# tailbrake.net
KiCad netlist of a schematic drawn in EAGLE
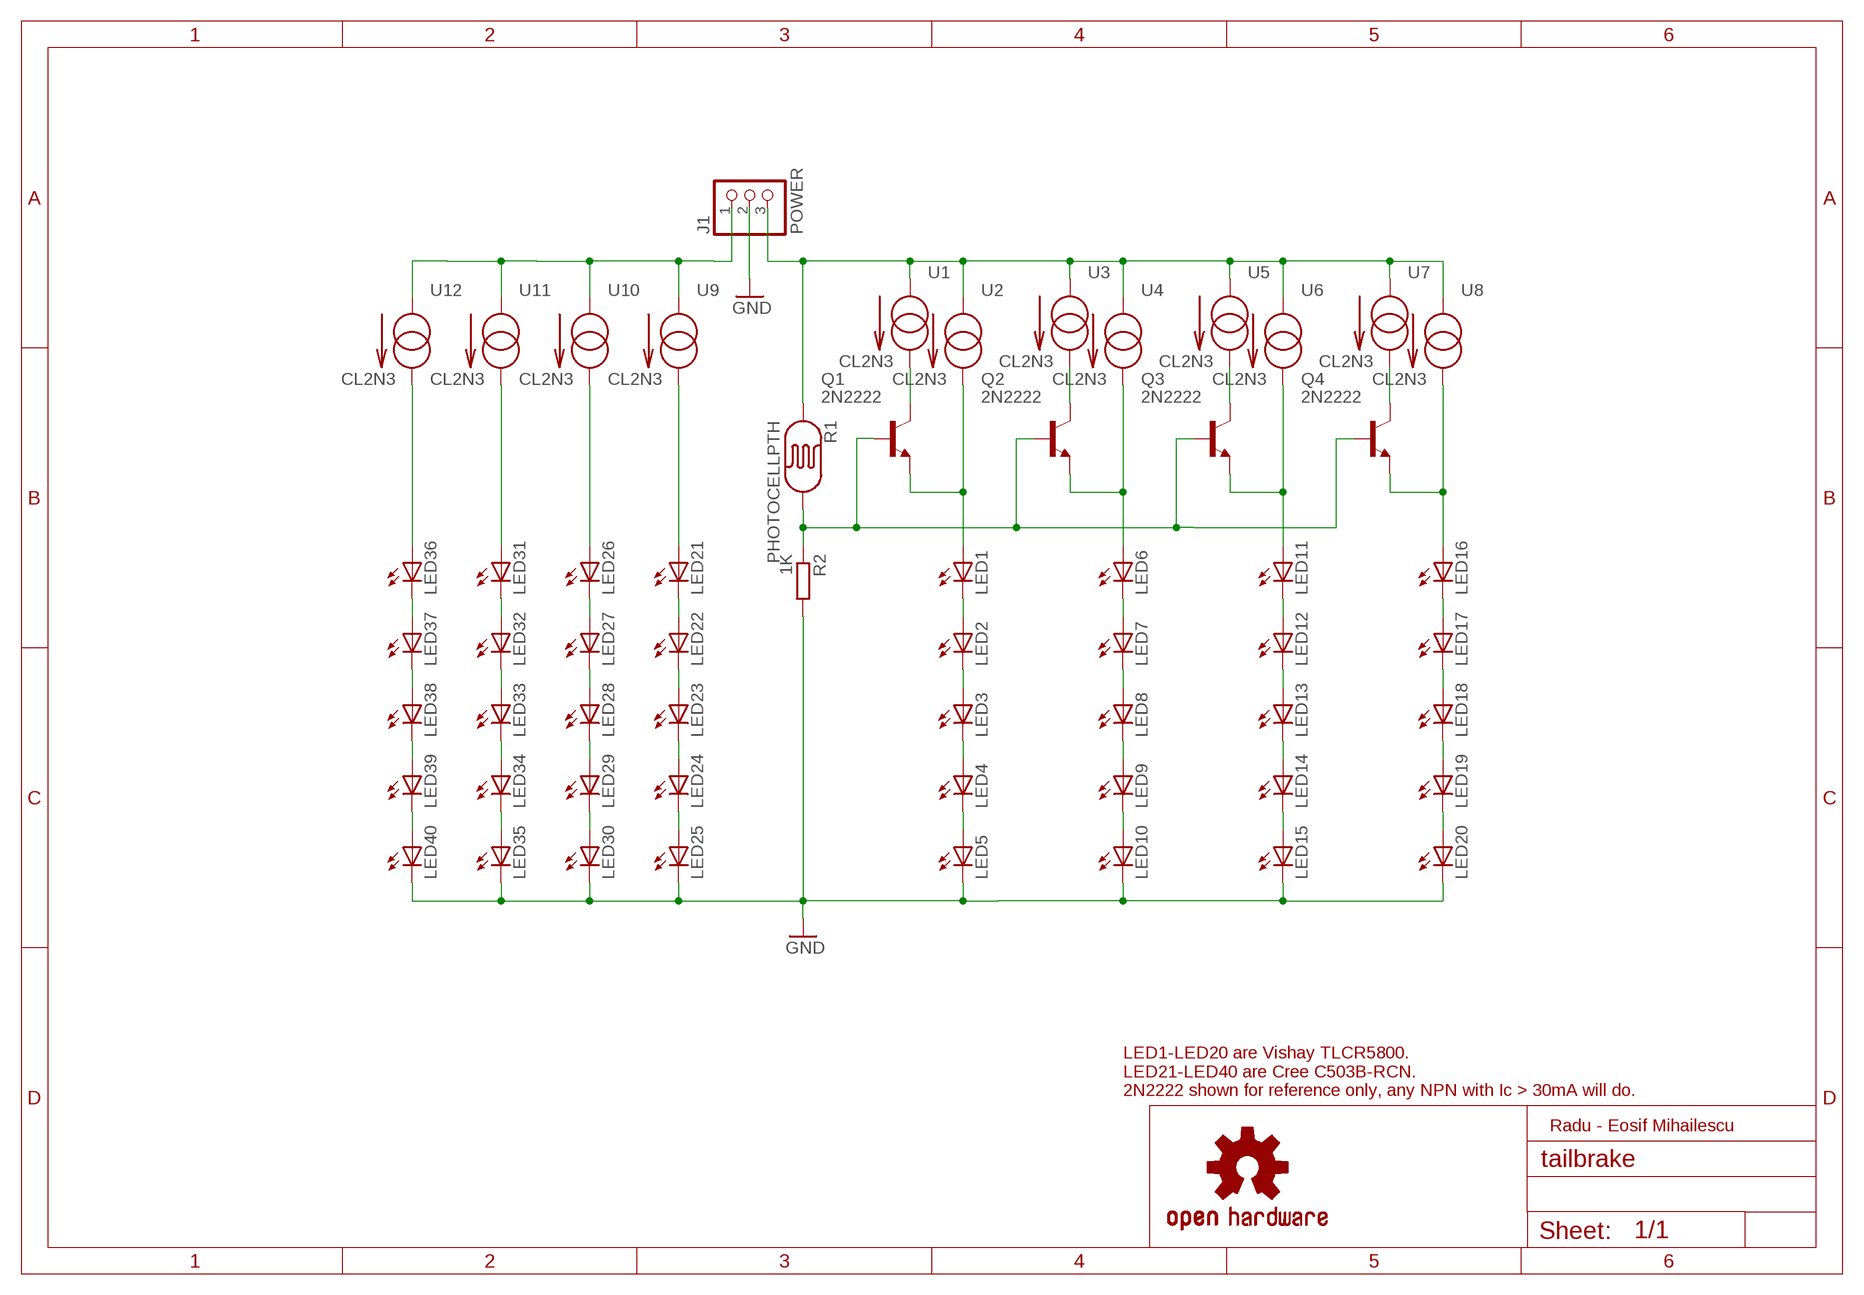
[diagram p0: schematic, sheet 1]

(export (version "E")
  (design (tool "Eeschema 10.0.6"))
  (components
    (comp (ref "J1")
      (value "POWER")
      (footprint "eagle-import:1X03_90")
      (libsource (lib "eagle-import") (part "PINHD-1X3/90"))
    )
    (comp (ref "LED1")
      (value "LED5MM")
      (footprint "eagle-import:LED5MM")
      (libsource (lib "eagle-import") (part "LED5MM"))
    )
    (comp (ref "LED2")
      (value "LED5MM")
      (footprint "eagle-import:LED5MM")
      (libsource (lib "eagle-import") (part "LED5MM"))
    )
    (comp (ref "LED3")
      (value "LED5MM")
      (footprint "eagle-import:LED5MM")
      (libsource (lib "eagle-import") (part "LED5MM"))
    )
    (comp (ref "LED4")
      (value "LED5MM")
      (footprint "eagle-import:LED5MM")
      (libsource (lib "eagle-import") (part "LED5MM"))
    )
    (comp (ref "LED5")
      (value "LED5MM")
      (footprint "eagle-import:LED5MM")
      (libsource (lib "eagle-import") (part "LED5MM"))
    )
    (comp (ref "LED6")
      (value "LED5MM")
      (footprint "eagle-import:LED5MM")
      (libsource (lib "eagle-import") (part "LED5MM"))
    )
    (comp (ref "LED7")
      (value "LED5MM")
      (footprint "eagle-import:LED5MM")
      (libsource (lib "eagle-import") (part "LED5MM"))
    )
    (comp (ref "LED8")
      (value "LED5MM")
      (footprint "eagle-import:LED5MM")
      (libsource (lib "eagle-import") (part "LED5MM"))
    )
    (comp (ref "LED9")
      (value "LED5MM")
      (footprint "eagle-import:LED5MM")
      (libsource (lib "eagle-import") (part "LED5MM"))
    )
    (comp (ref "LED10")
      (value "LED5MM")
      (footprint "eagle-import:LED5MM")
      (libsource (lib "eagle-import") (part "LED5MM"))
    )
    (comp (ref "LED11")
      (value "LED5MM")
      (footprint "eagle-import:LED5MM")
      (libsource (lib "eagle-import") (part "LED5MM"))
    )
    (comp (ref "LED12")
      (value "LED5MM")
      (footprint "eagle-import:LED5MM")
      (libsource (lib "eagle-import") (part "LED5MM"))
    )
    (comp (ref "LED13")
      (value "LED5MM")
      (footprint "eagle-import:LED5MM")
      (libsource (lib "eagle-import") (part "LED5MM"))
    )
    (comp (ref "LED14")
      (value "LED5MM")
      (footprint "eagle-import:LED5MM")
      (libsource (lib "eagle-import") (part "LED5MM"))
    )
    (comp (ref "LED15")
      (value "LED5MM")
      (footprint "eagle-import:LED5MM")
      (libsource (lib "eagle-import") (part "LED5MM"))
    )
    (comp (ref "LED16")
      (value "LED5MM")
      (footprint "eagle-import:LED5MM")
      (libsource (lib "eagle-import") (part "LED5MM"))
    )
    (comp (ref "LED17")
      (value "LED5MM")
      (footprint "eagle-import:LED5MM")
      (libsource (lib "eagle-import") (part "LED5MM"))
    )
    (comp (ref "LED18")
      (value "LED5MM")
      (footprint "eagle-import:LED5MM")
      (libsource (lib "eagle-import") (part "LED5MM"))
    )
    (comp (ref "LED19")
      (value "LED5MM")
      (footprint "eagle-import:LED5MM")
      (libsource (lib "eagle-import") (part "LED5MM"))
    )
    (comp (ref "LED20")
      (value "LED5MM")
      (footprint "eagle-import:LED5MM")
      (libsource (lib "eagle-import") (part "LED5MM"))
    )
    (comp (ref "LED21")
      (value "LED5MM")
      (footprint "eagle-import:LED5MM")
      (libsource (lib "eagle-import") (part "LED5MM"))
    )
    (comp (ref "LED22")
      (value "LED5MM")
      (footprint "eagle-import:LED5MM")
      (libsource (lib "eagle-import") (part "LED5MM"))
    )
    (comp (ref "LED23")
      (value "LED5MM")
      (footprint "eagle-import:LED5MM")
      (libsource (lib "eagle-import") (part "LED5MM"))
    )
    (comp (ref "LED24")
      (value "LED5MM")
      (footprint "eagle-import:LED5MM")
      (libsource (lib "eagle-import") (part "LED5MM"))
    )
    (comp (ref "LED25")
      (value "LED5MM")
      (footprint "eagle-import:LED5MM")
      (libsource (lib "eagle-import") (part "LED5MM"))
    )
    (comp (ref "LED26")
      (value "LED5MM")
      (footprint "eagle-import:LED5MM")
      (libsource (lib "eagle-import") (part "LED5MM"))
    )
    (comp (ref "LED27")
      (value "LED5MM")
      (footprint "eagle-import:LED5MM")
      (libsource (lib "eagle-import") (part "LED5MM"))
    )
    (comp (ref "LED28")
      (value "LED5MM")
      (footprint "eagle-import:LED5MM")
      (libsource (lib "eagle-import") (part "LED5MM"))
    )
    (comp (ref "LED29")
      (value "LED5MM")
      (footprint "eagle-import:LED5MM")
      (libsource (lib "eagle-import") (part "LED5MM"))
    )
    (comp (ref "LED30")
      (value "LED5MM")
      (footprint "eagle-import:LED5MM")
      (libsource (lib "eagle-import") (part "LED5MM"))
    )
    (comp (ref "LED31")
      (value "LED5MM")
      (footprint "eagle-import:LED5MM")
      (libsource (lib "eagle-import") (part "LED5MM"))
    )
    (comp (ref "LED32")
      (value "LED5MM")
      (footprint "eagle-import:LED5MM")
      (libsource (lib "eagle-import") (part "LED5MM"))
    )
    (comp (ref "LED33")
      (value "LED5MM")
      (footprint "eagle-import:LED5MM")
      (libsource (lib "eagle-import") (part "LED5MM"))
    )
    (comp (ref "LED34")
      (value "LED5MM")
      (footprint "eagle-import:LED5MM")
      (libsource (lib "eagle-import") (part "LED5MM"))
    )
    (comp (ref "LED35")
      (value "LED5MM")
      (footprint "eagle-import:LED5MM")
      (libsource (lib "eagle-import") (part "LED5MM"))
    )
    (comp (ref "LED36")
      (value "LED5MM")
      (footprint "eagle-import:LED5MM")
      (libsource (lib "eagle-import") (part "LED5MM"))
    )
    (comp (ref "LED37")
      (value "LED5MM")
      (footprint "eagle-import:LED5MM")
      (libsource (lib "eagle-import") (part "LED5MM"))
    )
    (comp (ref "LED38")
      (value "LED5MM")
      (footprint "eagle-import:LED5MM")
      (libsource (lib "eagle-import") (part "LED5MM"))
    )
    (comp (ref "LED39")
      (value "LED5MM")
      (footprint "eagle-import:LED5MM")
      (libsource (lib "eagle-import") (part "LED5MM"))
    )
    (comp (ref "LED40")
      (value "LED5MM")
      (footprint "eagle-import:LED5MM")
      (libsource (lib "eagle-import") (part "LED5MM"))
    )
    (comp (ref "LOGO1")
      (value "OSHW-LOGOL")
      (footprint "eagle-import:OSHW-LOGO-L")
      (libsource (lib "eagle-import") (part "OSHW-LOGOL"))
    )
    (comp (ref "Q1")
      (value "2N2222")
      (footprint "eagle-import:TO92-EBC")
      (libsource (lib "eagle-import") (part "-NPN-TO92-EBC2N2222"))
    )
    (comp (ref "Q2")
      (value "2N2222")
      (footprint "eagle-import:TO92-EBC")
      (libsource (lib "eagle-import") (part "-NPN-TO92-EBC2N2222"))
    )
    (comp (ref "Q3")
      (value "2N2222")
      (footprint "eagle-import:TO92-EBC")
      (libsource (lib "eagle-import") (part "-NPN-TO92-EBC2N2222"))
    )
    (comp (ref "Q4")
      (value "2N2222")
      (footprint "eagle-import:TO92-EBC")
      (libsource (lib "eagle-import") (part "-NPN-TO92-EBC2N2222"))
    )
    (comp (ref "R1")
      (value "PHOTOCELLPTH")
      (footprint "eagle-import:PHOTOCELL")
      (libsource (lib "eagle-import") (part "PHOTOCELLPTH"))
    )
    (comp (ref "R2")
      (value "1K")
      (footprint "eagle-import:0204_7")
      (libsource (lib "eagle-import") (part "R-EU_0204/7"))
    )
    (comp (ref "U1")
      (value "CL2N3")
      (footprint "eagle-import:TO-92")
      (libsource (lib "eagle-import") (part "CL2N3"))
    )
    (comp (ref "U2")
      (value "CL2N3")
      (footprint "eagle-import:TO-92")
      (libsource (lib "eagle-import") (part "CL2N3"))
    )
    (comp (ref "U3")
      (value "CL2N3")
      (footprint "eagle-import:TO-92")
      (libsource (lib "eagle-import") (part "CL2N3"))
    )
    (comp (ref "U4")
      (value "CL2N3")
      (footprint "eagle-import:TO-92")
      (libsource (lib "eagle-import") (part "CL2N3"))
    )
    (comp (ref "U5")
      (value "CL2N3")
      (footprint "eagle-import:TO-92")
      (libsource (lib "eagle-import") (part "CL2N3"))
    )
    (comp (ref "U6")
      (value "CL2N3")
      (footprint "eagle-import:TO-92")
      (libsource (lib "eagle-import") (part "CL2N3"))
    )
    (comp (ref "U7")
      (value "CL2N3")
      (footprint "eagle-import:TO-92")
      (libsource (lib "eagle-import") (part "CL2N3"))
    )
    (comp (ref "U8")
      (value "CL2N3")
      (footprint "eagle-import:TO-92")
      (libsource (lib "eagle-import") (part "CL2N3"))
    )
    (comp (ref "U9")
      (value "CL2N3")
      (footprint "eagle-import:TO-92")
      (libsource (lib "eagle-import") (part "CL2N3"))
    )
    (comp (ref "U10")
      (value "CL2N3")
      (footprint "eagle-import:TO-92")
      (libsource (lib "eagle-import") (part "CL2N3"))
    )
    (comp (ref "U11")
      (value "CL2N3")
      (footprint "eagle-import:TO-92")
      (libsource (lib "eagle-import") (part "CL2N3"))
    )
    (comp (ref "U12")
      (value "CL2N3")
      (footprint "eagle-import:TO-92")
      (libsource (lib "eagle-import") (part "CL2N3"))
    )
  )
  (nets
    (net (code "1") (name "GND") (class "Default")
      (node (ref "J1") (pin "2") (pinfunction "2_2") (pintype "passive"))
      (node (ref "LED10") (pin "K") (pinfunction "C_K") (pintype "passive"))
      (node (ref "LED15") (pin "K") (pinfunction "C_K") (pintype "passive"))
      (node (ref "LED20") (pin "K") (pinfunction "C_K") (pintype "passive"))
      (node (ref "LED25") (pin "K") (pinfunction "C_K") (pintype "passive"))
      (node (ref "LED30") (pin "K") (pinfunction "C_K") (pintype "passive"))
      (node (ref "LED35") (pin "K") (pinfunction "C_K") (pintype "passive"))
      (node (ref "LED40") (pin "K") (pinfunction "C_K") (pintype "passive"))
      (node (ref "LED5") (pin "K") (pinfunction "C_K") (pintype "passive"))
      (node (ref "R2") (pin "2") (pinfunction "2_2") (pintype "passive"))
    )
    (net (code "2") (name "Net-(LED1-C)") (class "Default")
      (node (ref "LED1") (pin "K") (pinfunction "C_K") (pintype "passive"))
      (node (ref "LED2") (pin "A") (pinfunction "A_A") (pintype "passive"))
    )
    (net (code "3") (name "Net-(LED2-C)") (class "Default")
      (node (ref "LED2") (pin "K") (pinfunction "C_K") (pintype "passive"))
      (node (ref "LED3") (pin "A") (pinfunction "A_A") (pintype "passive"))
    )
    (net (code "4") (name "Net-(LED3-C)") (class "Default")
      (node (ref "LED3") (pin "K") (pinfunction "C_K") (pintype "passive"))
      (node (ref "LED4") (pin "A") (pinfunction "A_A") (pintype "passive"))
    )
    (net (code "5") (name "Net-(LED4-C)") (class "Default")
      (node (ref "LED4") (pin "K") (pinfunction "C_K") (pintype "passive"))
      (node (ref "LED5") (pin "A") (pinfunction "A_A") (pintype "passive"))
    )
    (net (code "6") (name "Net-(LED6-C)") (class "Default")
      (node (ref "LED6") (pin "K") (pinfunction "C_K") (pintype "passive"))
      (node (ref "LED7") (pin "A") (pinfunction "A_A") (pintype "passive"))
    )
    (net (code "7") (name "Net-(LED7-C)") (class "Default")
      (node (ref "LED7") (pin "K") (pinfunction "C_K") (pintype "passive"))
      (node (ref "LED8") (pin "A") (pinfunction "A_A") (pintype "passive"))
    )
    (net (code "8") (name "Net-(LED8-C)") (class "Default")
      (node (ref "LED8") (pin "K") (pinfunction "C_K") (pintype "passive"))
      (node (ref "LED9") (pin "A") (pinfunction "A_A") (pintype "passive"))
    )
    (net (code "9") (name "Net-(LED9-C)") (class "Default")
      (node (ref "LED10") (pin "A") (pinfunction "A_A") (pintype "passive"))
      (node (ref "LED9") (pin "K") (pinfunction "C_K") (pintype "passive"))
    )
    (net (code "10") (name "Net-(LED11-C)") (class "Default")
      (node (ref "LED11") (pin "K") (pinfunction "C_K") (pintype "passive"))
      (node (ref "LED12") (pin "A") (pinfunction "A_A") (pintype "passive"))
    )
    (net (code "11") (name "Net-(LED12-C)") (class "Default")
      (node (ref "LED12") (pin "K") (pinfunction "C_K") (pintype "passive"))
      (node (ref "LED13") (pin "A") (pinfunction "A_A") (pintype "passive"))
    )
    (net (code "12") (name "Net-(LED13-C)") (class "Default")
      (node (ref "LED13") (pin "K") (pinfunction "C_K") (pintype "passive"))
      (node (ref "LED14") (pin "A") (pinfunction "A_A") (pintype "passive"))
    )
    (net (code "13") (name "Net-(LED14-C)") (class "Default")
      (node (ref "LED14") (pin "K") (pinfunction "C_K") (pintype "passive"))
      (node (ref "LED15") (pin "A") (pinfunction "A_A") (pintype "passive"))
    )
    (net (code "14") (name "Net-(LED16-C)") (class "Default")
      (node (ref "LED16") (pin "K") (pinfunction "C_K") (pintype "passive"))
      (node (ref "LED17") (pin "A") (pinfunction "A_A") (pintype "passive"))
    )
    (net (code "15") (name "Net-(LED17-C)") (class "Default")
      (node (ref "LED17") (pin "K") (pinfunction "C_K") (pintype "passive"))
      (node (ref "LED18") (pin "A") (pinfunction "A_A") (pintype "passive"))
    )
    (net (code "16") (name "Net-(LED18-C)") (class "Default")
      (node (ref "LED18") (pin "K") (pinfunction "C_K") (pintype "passive"))
      (node (ref "LED19") (pin "A") (pinfunction "A_A") (pintype "passive"))
    )
    (net (code "17") (name "Net-(LED19-C)") (class "Default")
      (node (ref "LED19") (pin "K") (pinfunction "C_K") (pintype "passive"))
      (node (ref "LED20") (pin "A") (pinfunction "A_A") (pintype "passive"))
    )
    (net (code "18") (name "Net-(LED21-C)") (class "Default")
      (node (ref "LED21") (pin "K") (pinfunction "C_K") (pintype "passive"))
      (node (ref "LED22") (pin "A") (pinfunction "A_A") (pintype "passive"))
    )
    (net (code "19") (name "Net-(LED22-C)") (class "Default")
      (node (ref "LED22") (pin "K") (pinfunction "C_K") (pintype "passive"))
      (node (ref "LED23") (pin "A") (pinfunction "A_A") (pintype "passive"))
    )
    (net (code "20") (name "Net-(LED23-C)") (class "Default")
      (node (ref "LED23") (pin "K") (pinfunction "C_K") (pintype "passive"))
      (node (ref "LED24") (pin "A") (pinfunction "A_A") (pintype "passive"))
    )
    (net (code "21") (name "Net-(LED24-C)") (class "Default")
      (node (ref "LED24") (pin "K") (pinfunction "C_K") (pintype "passive"))
      (node (ref "LED25") (pin "A") (pinfunction "A_A") (pintype "passive"))
    )
    (net (code "22") (name "Net-(LED26-C)") (class "Default")
      (node (ref "LED26") (pin "K") (pinfunction "C_K") (pintype "passive"))
      (node (ref "LED27") (pin "A") (pinfunction "A_A") (pintype "passive"))
    )
    (net (code "23") (name "Net-(LED27-C)") (class "Default")
      (node (ref "LED27") (pin "K") (pinfunction "C_K") (pintype "passive"))
      (node (ref "LED28") (pin "A") (pinfunction "A_A") (pintype "passive"))
    )
    (net (code "24") (name "Net-(LED28-C)") (class "Default")
      (node (ref "LED28") (pin "K") (pinfunction "C_K") (pintype "passive"))
      (node (ref "LED29") (pin "A") (pinfunction "A_A") (pintype "passive"))
    )
    (net (code "25") (name "Net-(LED29-C)") (class "Default")
      (node (ref "LED29") (pin "K") (pinfunction "C_K") (pintype "passive"))
      (node (ref "LED30") (pin "A") (pinfunction "A_A") (pintype "passive"))
    )
    (net (code "26") (name "Net-(LED31-C)") (class "Default")
      (node (ref "LED31") (pin "K") (pinfunction "C_K") (pintype "passive"))
      (node (ref "LED32") (pin "A") (pinfunction "A_A") (pintype "passive"))
    )
    (net (code "27") (name "Net-(LED32-C)") (class "Default")
      (node (ref "LED32") (pin "K") (pinfunction "C_K") (pintype "passive"))
      (node (ref "LED33") (pin "A") (pinfunction "A_A") (pintype "passive"))
    )
    (net (code "28") (name "Net-(LED33-C)") (class "Default")
      (node (ref "LED33") (pin "K") (pinfunction "C_K") (pintype "passive"))
      (node (ref "LED34") (pin "A") (pinfunction "A_A") (pintype "passive"))
    )
    (net (code "29") (name "Net-(LED34-C)") (class "Default")
      (node (ref "LED34") (pin "K") (pinfunction "C_K") (pintype "passive"))
      (node (ref "LED35") (pin "A") (pinfunction "A_A") (pintype "passive"))
    )
    (net (code "30") (name "Net-(LED36-C)") (class "Default")
      (node (ref "LED36") (pin "K") (pinfunction "C_K") (pintype "passive"))
      (node (ref "LED37") (pin "A") (pinfunction "A_A") (pintype "passive"))
    )
    (net (code "31") (name "Net-(LED37-C)") (class "Default")
      (node (ref "LED37") (pin "K") (pinfunction "C_K") (pintype "passive"))
      (node (ref "LED38") (pin "A") (pinfunction "A_A") (pintype "passive"))
    )
    (net (code "32") (name "Net-(LED38-C)") (class "Default")
      (node (ref "LED38") (pin "K") (pinfunction "C_K") (pintype "passive"))
      (node (ref "LED39") (pin "A") (pinfunction "A_A") (pintype "passive"))
    )
    (net (code "33") (name "Net-(LED39-C)") (class "Default")
      (node (ref "LED39") (pin "K") (pinfunction "C_K") (pintype "passive"))
      (node (ref "LED40") (pin "A") (pinfunction "A_A") (pintype "passive"))
    )
    (net (code "34") (name "Net-(R1-P$1)") (class "Default")
      (node (ref "J1") (pin "3") (pinfunction "3_3") (pintype "passive"))
      (node (ref "R1") (pin "1") (pinfunction "P$1_1") (pintype "bidirectional"))
      (node (ref "U1") (pin "1") (pinfunction "IN_1") (pintype "input"))
      (node (ref "U2") (pin "1") (pinfunction "IN_1") (pintype "input"))
      (node (ref "U3") (pin "1") (pinfunction "IN_1") (pintype "input"))
      (node (ref "U4") (pin "1") (pinfunction "IN_1") (pintype "input"))
      (node (ref "U5") (pin "1") (pinfunction "IN_1") (pintype "input"))
      (node (ref "U6") (pin "1") (pinfunction "IN_1") (pintype "input"))
      (node (ref "U7") (pin "1") (pinfunction "IN_1") (pintype "input"))
      (node (ref "U8") (pin "1") (pinfunction "IN_1") (pintype "input"))
    )
    (net (code "35") (name "Net-(R1-P$2)") (class "Default")
      (node (ref "Q1") (pin "B") (pinfunction "B_B") (pintype "passive"))
      (node (ref "Q2") (pin "B") (pinfunction "B_B") (pintype "passive"))
      (node (ref "Q3") (pin "B") (pinfunction "B_B") (pintype "passive"))
      (node (ref "Q4") (pin "B") (pinfunction "B_B") (pintype "passive"))
      (node (ref "R1") (pin "2") (pinfunction "P$2_2") (pintype "bidirectional"))
      (node (ref "R2") (pin "1") (pinfunction "1_1") (pintype "passive"))
    )
    (net (code "36") (name "Net-(U1-OUT)") (class "Default")
      (node (ref "Q1") (pin "C") (pinfunction "C_C") (pintype "passive"))
      (node (ref "U1") (pin "3") (pinfunction "OUT_3") (pintype "output"))
    )
    (net (code "37") (name "Net-(U2-OUT)") (class "Default")
      (node (ref "LED1") (pin "A") (pinfunction "A_A") (pintype "passive"))
      (node (ref "Q1") (pin "E") (pinfunction "E_E") (pintype "passive"))
      (node (ref "U2") (pin "3") (pinfunction "OUT_3") (pintype "output"))
    )
    (net (code "38") (name "Net-(U3-OUT)") (class "Default")
      (node (ref "Q2") (pin "C") (pinfunction "C_C") (pintype "passive"))
      (node (ref "U3") (pin "3") (pinfunction "OUT_3") (pintype "output"))
    )
    (net (code "39") (name "Net-(U4-OUT)") (class "Default")
      (node (ref "LED6") (pin "A") (pinfunction "A_A") (pintype "passive"))
      (node (ref "Q2") (pin "E") (pinfunction "E_E") (pintype "passive"))
      (node (ref "U4") (pin "3") (pinfunction "OUT_3") (pintype "output"))
    )
    (net (code "40") (name "Net-(U5-OUT)") (class "Default")
      (node (ref "Q3") (pin "C") (pinfunction "C_C") (pintype "passive"))
      (node (ref "U5") (pin "3") (pinfunction "OUT_3") (pintype "output"))
    )
    (net (code "41") (name "Net-(U6-OUT)") (class "Default")
      (node (ref "LED11") (pin "A") (pinfunction "A_A") (pintype "passive"))
      (node (ref "Q3") (pin "E") (pinfunction "E_E") (pintype "passive"))
      (node (ref "U6") (pin "3") (pinfunction "OUT_3") (pintype "output"))
    )
    (net (code "42") (name "Net-(U7-OUT)") (class "Default")
      (node (ref "Q4") (pin "C") (pinfunction "C_C") (pintype "passive"))
      (node (ref "U7") (pin "3") (pinfunction "OUT_3") (pintype "output"))
    )
    (net (code "43") (name "Net-(U8-OUT)") (class "Default")
      (node (ref "LED16") (pin "A") (pinfunction "A_A") (pintype "passive"))
      (node (ref "Q4") (pin "E") (pinfunction "E_E") (pintype "passive"))
      (node (ref "U8") (pin "3") (pinfunction "OUT_3") (pintype "output"))
    )
    (net (code "44") (name "Net-(U9-OUT)") (class "Default")
      (node (ref "LED21") (pin "A") (pinfunction "A_A") (pintype "passive"))
      (node (ref "U9") (pin "3") (pinfunction "OUT_3") (pintype "output"))
    )
    (net (code "45") (name "Net-(U10-IN)") (class "Default")
      (node (ref "J1") (pin "1") (pinfunction "1_1") (pintype "passive"))
      (node (ref "U10") (pin "1") (pinfunction "IN_1") (pintype "input"))
      (node (ref "U11") (pin "1") (pinfunction "IN_1") (pintype "input"))
      (node (ref "U12") (pin "1") (pinfunction "IN_1") (pintype "input"))
      (node (ref "U9") (pin "1") (pinfunction "IN_1") (pintype "input"))
    )
    (net (code "46") (name "Net-(U10-OUT)") (class "Default")
      (node (ref "LED26") (pin "A") (pinfunction "A_A") (pintype "passive"))
      (node (ref "U10") (pin "3") (pinfunction "OUT_3") (pintype "output"))
    )
    (net (code "47") (name "Net-(U11-OUT)") (class "Default")
      (node (ref "LED31") (pin "A") (pinfunction "A_A") (pintype "passive"))
      (node (ref "U11") (pin "3") (pinfunction "OUT_3") (pintype "output"))
    )
    (net (code "48") (name "Net-(U12-OUT)") (class "Default")
      (node (ref "LED36") (pin "A") (pinfunction "A_A") (pintype "passive"))
      (node (ref "U12") (pin "3") (pinfunction "OUT_3") (pintype "output"))
    )
  )
)
